# E200.net
KiCad netlist of a schematic drawn in EAGLE
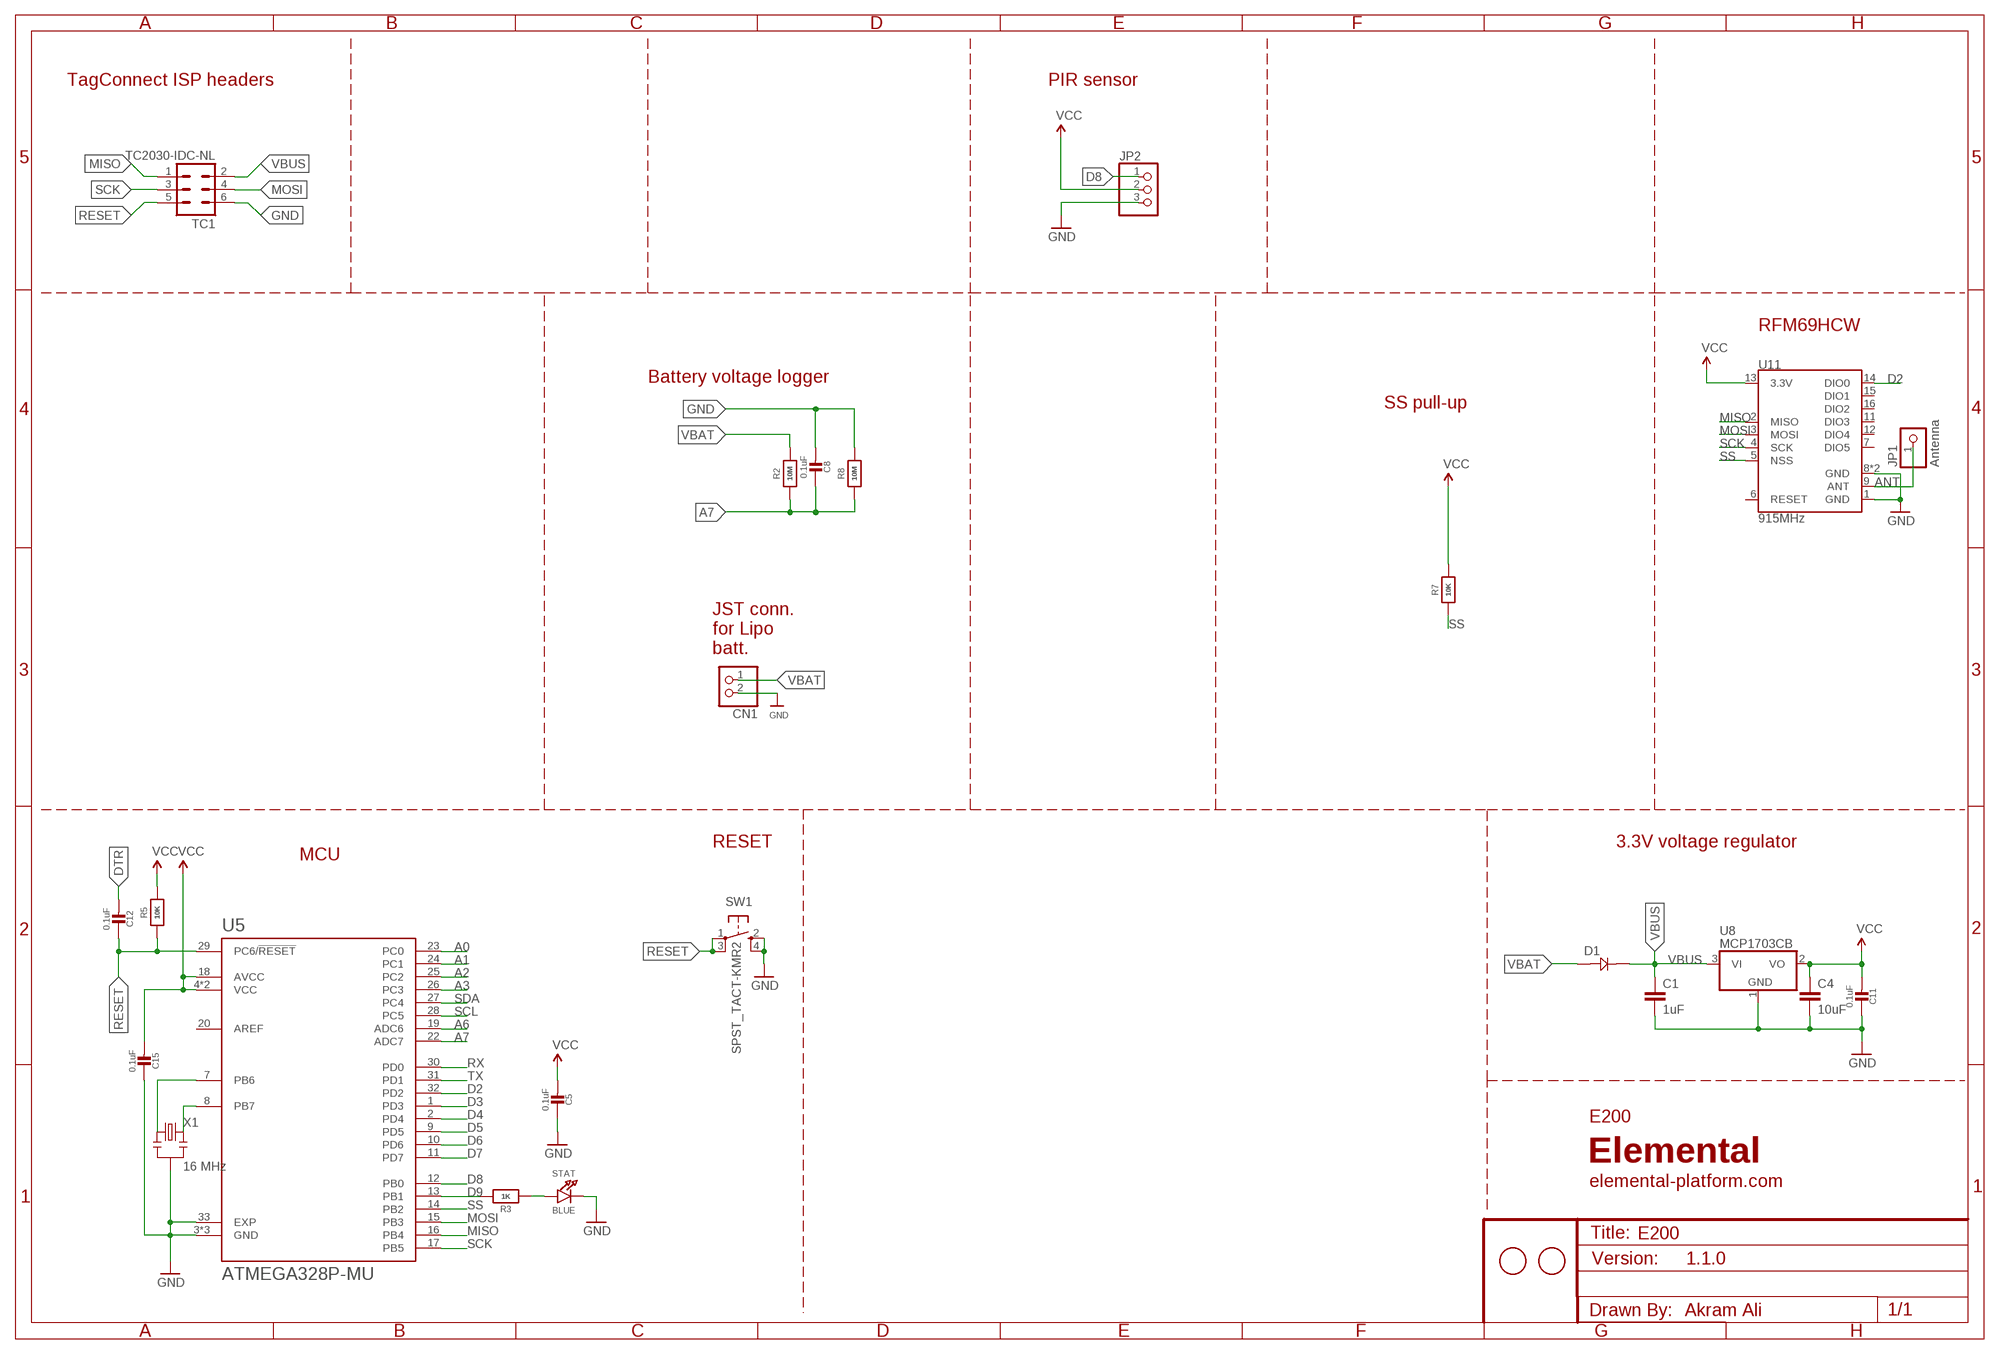
[diagram p0: schematic, sheet 1]

(export (version "E")
  (design (tool "Eeschema 10.0.6"))
  (components
    (comp (ref "C1")
      (value "1uF")
      (footprint "eagle-import:0805")
      (fields (field (name "MPN") "CC0805ZRY5V8BB105"))
      (libsource (lib "eagle-import") (part "CAP0805"))
    )
    (comp (ref "C4")
      (value "10uF")
      (footprint "eagle-import:0805")
      (fields (field (name "MPN") "CC0805KKX5R6BB106"))
      (libsource (lib "eagle-import") (part "CAP0805"))
    )
    (comp (ref "C5")
      (value "0.1uF")
      (footprint "eagle-import:MICROBUILDER__0402MP")
      (fields (field (name "MPN") "GRM155R71C104KA88J"))
      (libsource (lib "eagle-import") (part "MICROBUILDER_CAP_CERAMIC_0402MP"))
    )
    (comp (ref "C8")
      (value "0.1uF")
      (footprint "eagle-import:MICROBUILDER__0402MP")
      (fields (field (name "MPN") "GRM155R71C104KA88J"))
      (libsource (lib "eagle-import") (part "MICROBUILDER_CAP_CERAMIC_0402MP"))
    )
    (comp (ref "C11")
      (value "0.1uF")
      (footprint "eagle-import:MICROBUILDER__0402MP")
      (fields (field (name "MPN") "GRM155R71C104KA88J"))
      (libsource (lib "eagle-import") (part "MICROBUILDER_CAP_CERAMIC_0402MP"))
    )
    (comp (ref "C12")
      (value "0.1uF")
      (footprint "eagle-import:MICROBUILDER__0402MP")
      (fields (field (name "MPN") "GRM155R71C104KA88J"))
      (libsource (lib "eagle-import") (part "MICROBUILDER_CAP_CERAMIC_0402MP"))
    )
    (comp (ref "C15")
      (value "0.1uF")
      (footprint "eagle-import:MICROBUILDER__0402MP")
      (fields (field (name "MPN") "GRM155R71C104KA88J"))
      (libsource (lib "eagle-import") (part "MICROBUILDER_CAP_CERAMIC_0402MP"))
    )
    (comp (ref "CN1")
      (value "JST_2PIN-SMT-RA")
      (footprint "eagle-import:JST-PH-2-SMT-RA")
      (libsource (lib "eagle-import") (part "JST_2PIN-SMT-RA"))
    )
    (comp (ref "D1")
      (value "DIODE_SCHOTTKY0805-RES")
      (footprint "eagle-import:0805")
      (libsource (lib "eagle-import") (part "DIODE_SCHOTTKY0805-RES"))
    )
    (comp (ref "JP1")
      (value "Antenna")
      (footprint "eagle-import:1X01-CLEANBIG")
      (fields (field (name "MPN") "Helical antenna"))
      (libsource (lib "eagle-import") (part "PINHD-1X1CB"))
    )
    (comp (ref "JP2")
      (value "PINHD-1X3")
      (footprint "eagle-import:1X03")
      (libsource (lib "eagle-import") (part "PINHD-1X3"))
    )
    (comp (ref "R2")
      (value "10M")
      (footprint "eagle-import:MICROBUILDER__0402MP")
      (fields (field (name "MPN") "RC0402JR-0710KL"))
      (libsource (lib "eagle-import") (part "MICROBUILDER_RESISTOR_0402MP"))
    )
    (comp (ref "R3")
      (value "1K")
      (footprint "eagle-import:MICROBUILDER__0402MP")
      (fields (field (name "MPN") "RC0402JR-0710KL"))
      (libsource (lib "eagle-import") (part "MICROBUILDER_RESISTOR_0402MP"))
    )
    (comp (ref "R5")
      (value "10K")
      (footprint "eagle-import:MICROBUILDER__0402MP")
      (fields (field (name "MPN") "RC0402JR-0710KL"))
      (libsource (lib "eagle-import") (part "MICROBUILDER_RESISTOR_0402MP"))
    )
    (comp (ref "R7")
      (value "10K")
      (footprint "eagle-import:MICROBUILDER__0402MP")
      (fields (field (name "MPN") "RC0402JR-0710KL"))
      (libsource (lib "eagle-import") (part "MICROBUILDER_RESISTOR_0402MP"))
    )
    (comp (ref "R8")
      (value "10M")
      (footprint "eagle-import:MICROBUILDER__0402MP")
      (fields (field (name "MPN") "RC0402JR-0710KL"))
      (libsource (lib "eagle-import") (part "MICROBUILDER_RESISTOR_0402MP"))
    )
    (comp (ref "STAT")
      (value "BLUE")
      (footprint "eagle-import:CHIPLED_0805_NOOUTLINE")
      (libsource (lib "eagle-import") (part "LED0805_NOOUTLINE"))
    )
    (comp (ref "SW1")
      (value "SPST_TACT-KMR2")
      (footprint "eagle-import:KMR2")
      (libsource (lib "eagle-import") (part "SPST_TACT-KMR2"))
    )
    (comp (ref "TC1")
      (value "TC2030-IDC-NL")
      (footprint "eagle-import:TC2030-IDC-NL")
      (libsource (lib "eagle-import") (part "TC2030-IDC-NL"))
    )
    (comp (ref "U$1")
      (value "FIDUCIAL")
      (footprint "eagle-import:FIDUCIAL_1MM")
      (libsource (lib "eagle-import") (part "FIDUCIAL"))
    )
    (comp (ref "U$7")
      (value "FIDUCIAL")
      (footprint "eagle-import:FIDUCIAL_1MM")
      (libsource (lib "eagle-import") (part "FIDUCIAL"))
    )
    (comp (ref "U5")
      (value "ATMEGA328P-MU")
      (footprint "eagle-import:QFN50P500X500X100-33N")
      (fields (field (name "MF") "Atmel"))
      (libsource (lib "eagle-import") (part "ATMEGA328P-MU"))
    )
    (comp (ref "U8")
      (value "MCP1703CB")
      (footprint "eagle-import:SOT23")
      (fields (field (name "MPN") "MCP1703T-3302E/CB"))
      (libsource (lib "eagle-import") (part "MCP1703CB"))
    )
    (comp (ref "U11")
      (value "915MHz")
      (footprint "eagle-import:RFM69HCW-XXXS2")
      (fields (field (name "MPN") "RFM69HCW"))
      (libsource (lib "eagle-import") (part "RFM69HCW-915"))
    )
    (comp (ref "X1")
      (value "16 MHz")
      (footprint "eagle-import:RESONATOR-SMD")
      (fields (field (name "MPN") "CSTCE16M0V53-R0"))
      (libsource (lib "eagle-import") (part "RESONATORSMD"))
    )
  )
  (nets
    (net (code "1") (name "/A0") (class "Default")
      (node (ref "U5") (pin "23") (pinfunction "PC0_23") (pintype "bidirectional"))
    )
    (net (code "2") (name "/A1") (class "Default")
      (node (ref "U5") (pin "24") (pinfunction "PC1_24") (pintype "bidirectional"))
    )
    (net (code "3") (name "/A2") (class "Default")
      (node (ref "U5") (pin "25") (pinfunction "PC2_25") (pintype "bidirectional"))
    )
    (net (code "4") (name "/A3") (class "Default")
      (node (ref "U5") (pin "26") (pinfunction "PC3_26") (pintype "bidirectional"))
    )
    (net (code "5") (name "/A6") (class "Default")
      (node (ref "U5") (pin "19") (pinfunction "ADC6_19") (pintype "bidirectional"))
    )
    (net (code "6") (name "/ANT") (class "Default")
      (node (ref "JP1") (pin "1") (pinfunction "1_1") (pintype "passive"))
      (node (ref "U11") (pin "9") (pinfunction "ANT_9") (pintype "passive"))
    )
    (net (code "7") (name "/D2") (class "Default")
      (node (ref "U11") (pin "14") (pinfunction "DIO0_14") (pintype "bidirectional"))
      (node (ref "U5") (pin "32") (pinfunction "PD2_32") (pintype "bidirectional"))
    )
    (net (code "8") (name "/D3") (class "Default")
      (node (ref "U5") (pin "1") (pinfunction "PD3_1") (pintype "bidirectional"))
    )
    (net (code "9") (name "/D4") (class "Default")
      (node (ref "U5") (pin "2") (pinfunction "PD4_2") (pintype "bidirectional"))
    )
    (net (code "10") (name "/D5") (class "Default")
      (node (ref "U5") (pin "9") (pinfunction "PD5_9") (pintype "bidirectional"))
    )
    (net (code "11") (name "/D6") (class "Default")
      (node (ref "U5") (pin "10") (pinfunction "PD6_10") (pintype "bidirectional"))
    )
    (net (code "12") (name "/D7") (class "Default")
      (node (ref "U5") (pin "11") (pinfunction "PD7_11") (pintype "bidirectional"))
    )
    (net (code "13") (name "/D9") (class "Default")
      (node (ref "R3") (pin "2") (pinfunction "2_2") (pintype "passive"))
      (node (ref "U5") (pin "13") (pinfunction "PB1_13") (pintype "bidirectional"))
    )
    (net (code "14") (name "/RX") (class "Default")
      (node (ref "U5") (pin "30") (pinfunction "PD0_30") (pintype "bidirectional"))
    )
    (net (code "15") (name "/SCL") (class "Default")
      (node (ref "U5") (pin "28") (pinfunction "PC5_28") (pintype "bidirectional"))
    )
    (net (code "16") (name "/SDA") (class "Default")
      (node (ref "U5") (pin "27") (pinfunction "PC4_27") (pintype "bidirectional"))
    )
    (net (code "17") (name "/SS") (class "Default")
      (node (ref "R7") (pin "1") (pinfunction "1_1") (pintype "passive"))
      (node (ref "U11") (pin "5") (pinfunction "NSS_5") (pintype "input"))
      (node (ref "U5") (pin "14") (pinfunction "PB2_14") (pintype "bidirectional"))
    )
    (net (code "18") (name "/TX") (class "Default")
      (node (ref "U5") (pin "31") (pinfunction "PD1_31") (pintype "bidirectional"))
    )
    (net (code "19") (name "A7") (class "Default")
      (node (ref "C8") (pin "1") (pinfunction "1_1") (pintype "passive"))
      (node (ref "R2") (pin "1") (pinfunction "1_1") (pintype "passive"))
      (node (ref "R8") (pin "1") (pinfunction "1_1") (pintype "passive"))
      (node (ref "U5") (pin "22") (pinfunction "ADC7_22") (pintype "bidirectional"))
    )
    (net (code "20") (name "D8") (class "Default")
      (node (ref "JP2") (pin "1") (pinfunction "1_1") (pintype "passive"))
      (node (ref "U5") (pin "12") (pinfunction "PB0_12") (pintype "bidirectional"))
    )
    (net (code "21") (name "DTR") (class "Default")
      (node (ref "C12") (pin "2") (pinfunction "2_2") (pintype "passive"))
    )
    (net (code "22") (name "GND") (class "Default")
      (node (ref "C1") (pin "2") (pinfunction "2_2") (pintype "passive"))
      (node (ref "C11") (pin "1") (pinfunction "1_1") (pintype "passive"))
      (node (ref "C15") (pin "1") (pinfunction "1_1") (pintype "passive"))
      (node (ref "C4") (pin "2") (pinfunction "2_2") (pintype "passive"))
      (node (ref "C5") (pin "1") (pinfunction "1_1") (pintype "passive"))
      (node (ref "C8") (pin "2") (pinfunction "2_2") (pintype "passive"))
      (node (ref "CN1") (pin "2") (pinfunction "1_2") (pintype "passive"))
      (node (ref "JP2") (pin "3") (pinfunction "3_3") (pintype "passive"))
      (node (ref "R8") (pin "2") (pinfunction "2_2") (pintype "passive"))
      (node (ref "STAT") (pin "C") (pinfunction "C_C") (pintype "passive"))
      (node (ref "SW1") (pin "2") (pinfunction "S_2") (pintype "passive"))
      (node (ref "SW1") (pin "4") (pinfunction "S1_4") (pintype "passive"))
      (node (ref "TC1") (pin "6") (pinfunction "6_6") (pintype "passive"))
      (node (ref "U11") (pin "1") (pinfunction "GND_1") (pintype "power_in"))
      (node (ref "U11") (pin "10") (pinfunction "GND_10") (pintype "power_in"))
      (node (ref "U11") (pin "8") (pinfunction "GND_8") (pintype "power_in"))
      (node (ref "U5") (pin "21") (pinfunction "GND_21") (pintype "power_in"))
      (node (ref "U5") (pin "3") (pinfunction "GND_3") (pintype "power_in"))
      (node (ref "U5") (pin "33") (pinfunction "EXP_33") (pintype "power_in"))
      (node (ref "U5") (pin "5") (pinfunction "GND_5") (pintype "power_in"))
      (node (ref "U8") (pin "1") (pinfunction "GND_1") (pintype "passive"))
      (node (ref "X1") (pin "2") (pinfunction "2_2") (pintype "passive"))
    )
    (net (code "23") (name "MISO") (class "Default")
      (node (ref "TC1") (pin "1") (pinfunction "1_1") (pintype "passive"))
      (node (ref "U11") (pin "2") (pinfunction "MISO_2") (pintype "bidirectional"))
      (node (ref "U5") (pin "16") (pinfunction "PB4_16") (pintype "bidirectional"))
    )
    (net (code "24") (name "MOSI") (class "Default")
      (node (ref "TC1") (pin "4") (pinfunction "4_4") (pintype "passive"))
      (node (ref "U11") (pin "3") (pinfunction "MOSI_3") (pintype "input"))
      (node (ref "U5") (pin "15") (pinfunction "PB3_15") (pintype "bidirectional"))
    )
    (net (code "25") (name "Net-(R3-Pad1)") (class "Default")
      (node (ref "R3") (pin "1") (pinfunction "1_1") (pintype "passive"))
      (node (ref "STAT") (pin "A") (pinfunction "A_A") (pintype "passive"))
    )
    (net (code "26") (name "Net-(U5-PB6)") (class "Default")
      (node (ref "U5") (pin "7") (pinfunction "PB6_7") (pintype "bidirectional"))
      (node (ref "X1") (pin "1") (pinfunction "1_1") (pintype "passive"))
    )
    (net (code "27") (name "Net-(U5-PB7)") (class "Default")
      (node (ref "U5") (pin "8") (pinfunction "PB7_8") (pintype "bidirectional"))
      (node (ref "X1") (pin "3") (pinfunction "3_3") (pintype "passive"))
    )
    (net (code "28") (name "RESET") (class "Default")
      (node (ref "C12") (pin "1") (pinfunction "1_1") (pintype "passive"))
      (node (ref "R5") (pin "1") (pinfunction "1_1") (pintype "passive"))
      (node (ref "SW1") (pin "1") (pinfunction "P_1") (pintype "passive"))
      (node (ref "SW1") (pin "3") (pinfunction "P1_3") (pintype "passive"))
      (node (ref "TC1") (pin "5") (pinfunction "5_5") (pintype "passive"))
      (node (ref "U5") (pin "29") (pinfunction "PC6/~{RESET}_29") (pintype "bidirectional"))
    )
    (net (code "29") (name "SCK") (class "Default")
      (node (ref "TC1") (pin "3") (pinfunction "3_3") (pintype "passive"))
      (node (ref "U11") (pin "4") (pinfunction "SCK_4") (pintype "input"))
      (node (ref "U5") (pin "17") (pinfunction "PB5_17") (pintype "bidirectional"))
    )
    (net (code "30") (name "VBAT") (class "Default")
      (node (ref "CN1") (pin "1") (pinfunction "2_1") (pintype "passive"))
      (node (ref "D1") (pin "1") (pinfunction "1_1") (pintype "passive"))
      (node (ref "R2") (pin "2") (pinfunction "2_2") (pintype "passive"))
    )
    (net (code "31") (name "VBUS") (class "Default")
      (node (ref "C1") (pin "1") (pinfunction "1_1") (pintype "passive"))
      (node (ref "D1") (pin "2") (pinfunction "2_2") (pintype "passive"))
      (node (ref "TC1") (pin "2") (pinfunction "2_2") (pintype "passive"))
      (node (ref "U8") (pin "3") (pinfunction "VI_3") (pintype "input"))
    )
    (net (code "32") (name "VCC") (class "Default")
      (node (ref "C11") (pin "2") (pinfunction "2_2") (pintype "passive"))
      (node (ref "C15") (pin "2") (pinfunction "2_2") (pintype "passive"))
      (node (ref "C4") (pin "1") (pinfunction "1_1") (pintype "passive"))
      (node (ref "C5") (pin "2") (pinfunction "2_2") (pintype "passive"))
      (node (ref "JP2") (pin "2") (pinfunction "2_2") (pintype "passive"))
      (node (ref "R5") (pin "2") (pinfunction "2_2") (pintype "passive"))
      (node (ref "R7") (pin "2") (pinfunction "2_2") (pintype "passive"))
      (node (ref "U11") (pin "13") (pinfunction "3.3V_13") (pintype "power_in"))
      (node (ref "U5") (pin "18") (pinfunction "AVCC_18") (pintype "power_in"))
      (node (ref "U5") (pin "4") (pinfunction "VCC_4") (pintype "power_in"))
      (node (ref "U5") (pin "6") (pinfunction "VCC_6") (pintype "power_in"))
      (node (ref "U8") (pin "2") (pinfunction "VO_2") (pintype "passive"))
    )
    (net (code "33") (name "unconnected-(U5-AREF-Pad20)") (class "Default")
      (node (ref "U5") (pin "20") (pinfunction "AREF_20") (pintype "input"))
    )
    (net (code "34") (name "unconnected-(U11-DIO1-Pad15)") (class "Default")
      (node (ref "U11") (pin "15") (pinfunction "DIO1_15") (pintype "bidirectional"))
    )
    (net (code "35") (name "unconnected-(U11-DIO2-Pad16)") (class "Default")
      (node (ref "U11") (pin "16") (pinfunction "DIO2_16") (pintype "bidirectional"))
    )
    (net (code "36") (name "unconnected-(U11-DIO3-Pad11)") (class "Default")
      (node (ref "U11") (pin "11") (pinfunction "DIO3_11") (pintype "bidirectional"))
    )
    (net (code "37") (name "unconnected-(U11-DIO4-Pad12)") (class "Default")
      (node (ref "U11") (pin "12") (pinfunction "DIO4_12") (pintype "bidirectional"))
    )
    (net (code "38") (name "unconnected-(U11-DIO5-Pad7)") (class "Default")
      (node (ref "U11") (pin "7") (pinfunction "DIO5_7") (pintype "bidirectional"))
    )
    (net (code "39") (name "unconnected-(U11-RESET-Pad6)") (class "Default")
      (node (ref "U11") (pin "6") (pinfunction "RESET_6") (pintype "input"))
    )
  )
)
